# Projet_electronique_final_construct-_PIC.net
KiCad netlist of a schematic drawn in EAGLE
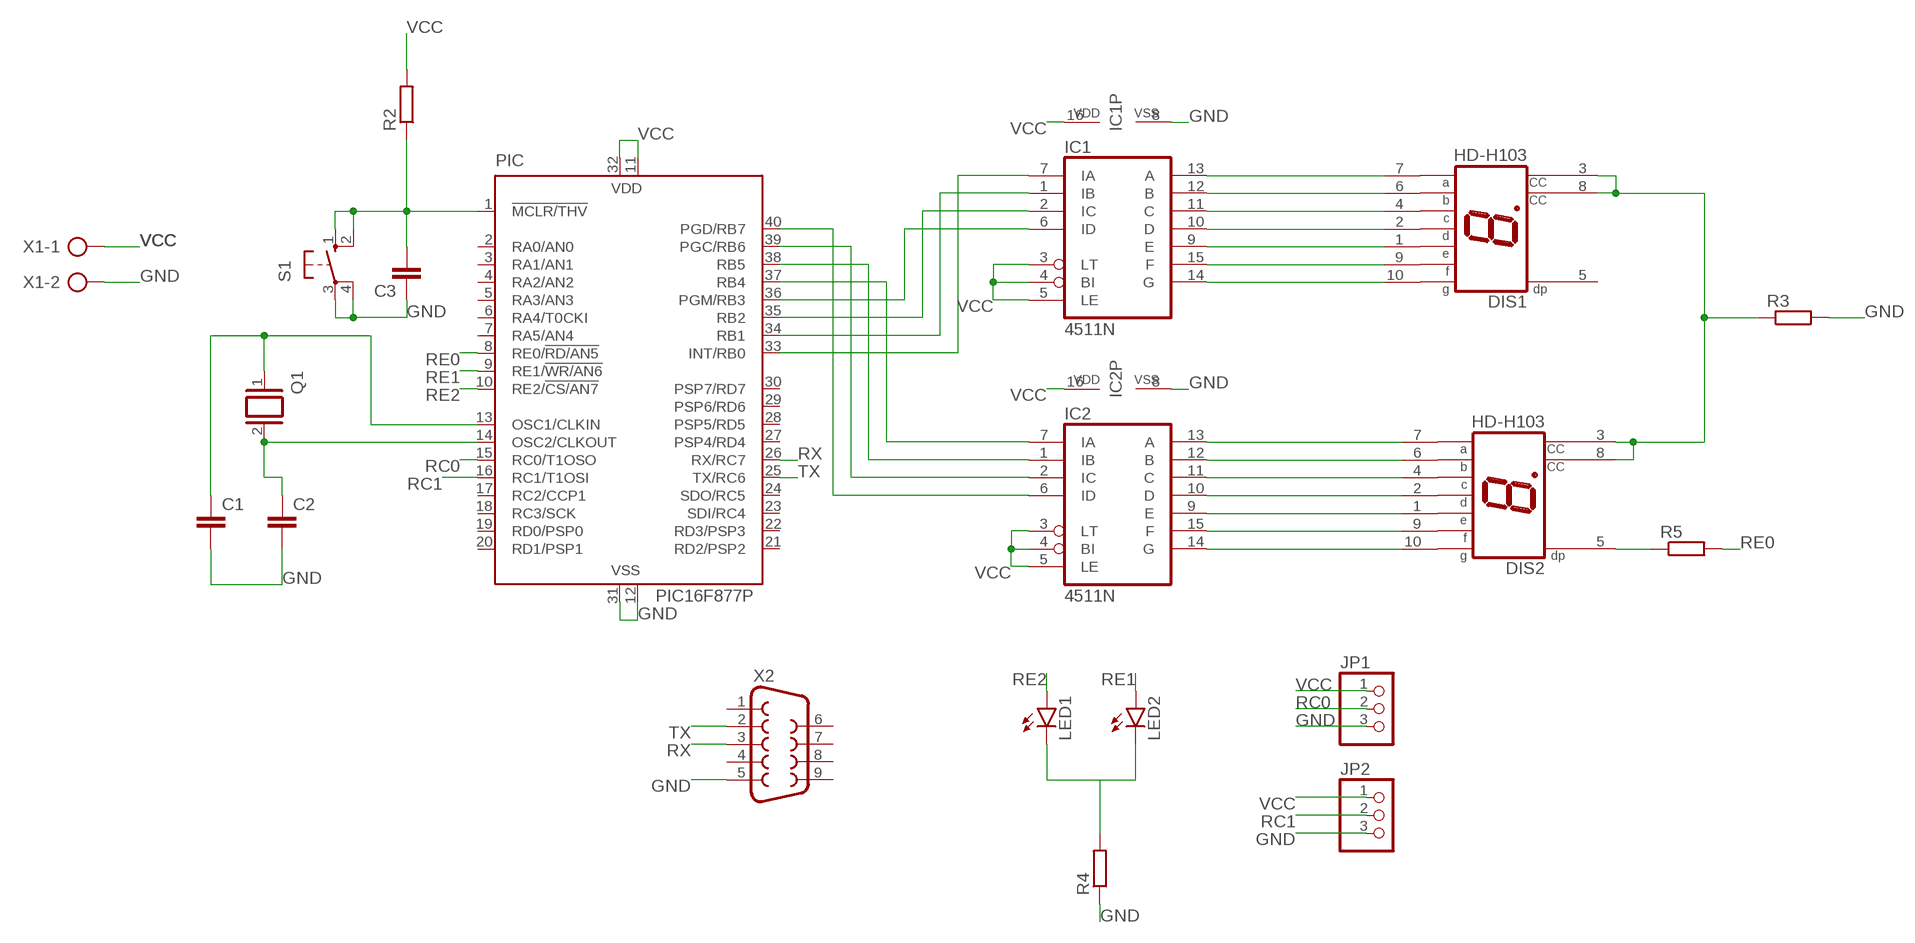
[diagram p0: schematic, sheet 1]

(export (version "E")
  (design (tool "Eeschema 10.0.6"))
  (components
    (comp (ref "C1")
      (value "C-EU025-025X050")
      (footprint "eagle-import:C025-025X050")
      (libsource (lib "eagle-import") (part "C-EU025-025X050"))
    )
    (comp (ref "C2")
      (value "C-EU025-025X050")
      (footprint "eagle-import:C025-025X050")
      (libsource (lib "eagle-import") (part "C-EU025-025X050"))
    )
    (comp (ref "C3")
      (value "C-EU025-025X050")
      (footprint "eagle-import:C025-025X050")
      (libsource (lib "eagle-import") (part "C-EU025-025X050"))
    )
    (comp (ref "DIS1")
      (value "HD-H103")
      (footprint "eagle-import:HDSP-M")
      (libsource (lib "eagle-import") (part "HD-H103"))
    )
    (comp (ref "DIS2")
      (value "HD-H103")
      (footprint "eagle-import:HDSP-M")
      (libsource (lib "eagle-import") (part "HD-H103"))
    )
    (comp (ref "IC1")
      (value "4511N")
      (footprint "eagle-import:DIL16")
      (libsource (lib "eagle-import") (part "4511N"))
    )
    (comp (ref "IC2")
      (value "4511N")
      (footprint "eagle-import:DIL16")
      (libsource (lib "eagle-import") (part "4511N"))
    )
    (comp (ref "JP1")
      (value "PINHD-1X3")
      (footprint "eagle-import:1X03")
      (libsource (lib "eagle-import") (part "PINHD-1X3"))
    )
    (comp (ref "JP2")
      (value "PINHD-1X3")
      (footprint "eagle-import:1X03")
      (libsource (lib "eagle-import") (part "PINHD-1X3"))
    )
    (comp (ref "LED1")
      (value "LED5MM")
      (footprint "eagle-import:LED5MM")
      (libsource (lib "eagle-import") (part "LED5MM"))
    )
    (comp (ref "LED2")
      (value "LED5MM")
      (footprint "eagle-import:LED5MM")
      (libsource (lib "eagle-import") (part "LED5MM"))
    )
    (comp (ref "PIC")
      (value "PIC16F877P")
      (footprint "eagle-import:DIL40")
      (fields (field (name "MF") "MICROCHIP") (field (name "MPN") "PIC16F877-04/P"))
      (libsource (lib "eagle-import") (part "PIC16F87P7"))
    )
    (comp (ref "Q1")
      (value "XTAL/S")
      (footprint "eagle-import:QS")
      (libsource (lib "eagle-import") (part "XTAL/S"))
    )
    (comp (ref "R2")
      (value "R-EU_0207/10")
      (footprint "eagle-import:0207_10")
      (libsource (lib "eagle-import") (part "R-EU_0207/10"))
    )
    (comp (ref "R3")
      (value "R-EU_0207/10")
      (footprint "eagle-import:0207_10")
      (libsource (lib "eagle-import") (part "R-EU_0207/10"))
    )
    (comp (ref "R4")
      (value "R-EU_0207/10")
      (footprint "eagle-import:0207_10")
      (libsource (lib "eagle-import") (part "R-EU_0207/10"))
    )
    (comp (ref "R5")
      (value "R-EU_0207/10")
      (footprint "eagle-import:0207_10")
      (libsource (lib "eagle-import") (part "R-EU_0207/10"))
    )
    (comp (ref "S1")
      (value "10-XX")
      (footprint "eagle-import:B3F-10XX")
      (fields (field (name "MPN") "B3F-1000"))
      (libsource (lib "eagle-import") (part "10-XX"))
    )
    (comp (ref "X1")
      (value "AK300/2")
      (footprint "eagle-import:AK300_2")
      (libsource (lib "eagle-import") (part "AK300/2"))
    )
    (comp (ref "X2")
      (value "F09H")
      (footprint "eagle-import:F09H")
      (libsource (lib "eagle-import") (part "F09H"))
    )
  )
  (nets
    (net (code "1") (name "/GND") (class "Default")
      (node (ref "C1") (pin "2") (pinfunction "2_2") (pintype "passive"))
      (node (ref "C2") (pin "2") (pinfunction "2_2") (pintype "passive"))
      (node (ref "C3") (pin "1") (pinfunction "1_1") (pintype "passive"))
      (node (ref "IC1") (pin "8") (pinfunction "VSS_8") (pintype "power_in"))
      (node (ref "IC2") (pin "8") (pinfunction "VSS_8") (pintype "power_in"))
      (node (ref "JP1") (pin "3") (pinfunction "3_3") (pintype "passive"))
      (node (ref "JP2") (pin "3") (pinfunction "3_3") (pintype "passive"))
      (node (ref "PIC") (pin "12") (pinfunction "VSS_12") (pintype "power_in"))
      (node (ref "PIC") (pin "31") (pinfunction "VSS_31") (pintype "power_in"))
      (node (ref "R3") (pin "2") (pinfunction "2_2") (pintype "passive"))
      (node (ref "R4") (pin "1") (pinfunction "1_1") (pintype "passive"))
      (node (ref "S1") (pin "3") (pinfunction "P_3") (pintype "passive"))
      (node (ref "S1") (pin "4") (pinfunction "P1_4") (pintype "passive"))
      (node (ref "X1") (pin "2") (pinfunction "KL_2") (pintype "passive"))
      (node (ref "X2") (pin "5") (pinfunction "5_5") (pintype "passive"))
    )
    (net (code "2") (name "/RC0") (class "Default")
      (node (ref "JP1") (pin "2") (pinfunction "2_2") (pintype "passive"))
      (node (ref "PIC") (pin "15") (pinfunction "RC0/T1OSO_15") (pintype "bidirectional"))
    )
    (net (code "3") (name "/RC1") (class "Default")
      (node (ref "JP2") (pin "2") (pinfunction "2_2") (pintype "passive"))
      (node (ref "PIC") (pin "16") (pinfunction "RC1/T1OSI_16") (pintype "bidirectional"))
    )
    (net (code "4") (name "/RE0") (class "Default")
      (node (ref "PIC") (pin "8") (pinfunction "RE0/~{RD/AN5}_8") (pintype "bidirectional"))
      (node (ref "R5") (pin "2") (pinfunction "2_2") (pintype "passive"))
    )
    (net (code "5") (name "/RE1") (class "Default")
      (node (ref "LED2") (pin "A") (pinfunction "A_A") (pintype "passive"))
      (node (ref "PIC") (pin "9") (pinfunction "RE1/~{WR/AN6}_9") (pintype "bidirectional"))
    )
    (net (code "6") (name "/RE2") (class "Default")
      (node (ref "LED1") (pin "A") (pinfunction "A_A") (pintype "passive"))
      (node (ref "PIC") (pin "10") (pinfunction "RE2/~{CS/AN7}_10") (pintype "bidirectional"))
    )
    (net (code "7") (name "/RX") (class "Default")
      (node (ref "PIC") (pin "26") (pinfunction "RX/RC7_26") (pintype "bidirectional"))
      (node (ref "X2") (pin "3") (pinfunction "3_3") (pintype "passive"))
    )
    (net (code "8") (name "/TX") (class "Default")
      (node (ref "PIC") (pin "25") (pinfunction "TX/RC6_25") (pintype "bidirectional"))
      (node (ref "X2") (pin "2") (pinfunction "2_2") (pintype "passive"))
    )
    (net (code "9") (name "/VCC") (class "Default")
      (node (ref "IC1") (pin "16") (pinfunction "VDD_16") (pintype "power_in"))
      (node (ref "IC1") (pin "3") (pinfunction "LT_3") (pintype "input"))
      (node (ref "IC1") (pin "4") (pinfunction "BI_4") (pintype "input"))
      (node (ref "IC1") (pin "5") (pinfunction "LE_5") (pintype "input"))
      (node (ref "IC2") (pin "16") (pinfunction "VDD_16") (pintype "power_in"))
      (node (ref "IC2") (pin "3") (pinfunction "LT_3") (pintype "input"))
      (node (ref "IC2") (pin "4") (pinfunction "BI_4") (pintype "input"))
      (node (ref "IC2") (pin "5") (pinfunction "LE_5") (pintype "input"))
      (node (ref "JP1") (pin "1") (pinfunction "1_1") (pintype "passive"))
      (node (ref "JP2") (pin "1") (pinfunction "1_1") (pintype "passive"))
      (node (ref "PIC") (pin "11") (pinfunction "VDD_11") (pintype "power_in"))
      (node (ref "PIC") (pin "32") (pinfunction "VDD_32") (pintype "power_in"))
      (node (ref "R2") (pin "2") (pinfunction "2_2") (pintype "passive"))
      (node (ref "X1") (pin "1") (pinfunction "KL_1") (pintype "passive"))
    )
    (net (code "10") (name "Net-(DIS1-A)") (class "Default")
      (node (ref "DIS1") (pin "7") (pinfunction "A_7") (pintype "passive"))
      (node (ref "IC1") (pin "13") (pinfunction "A_13") (pintype "output"))
    )
    (net (code "11") (name "Net-(DIS1-B)") (class "Default")
      (node (ref "DIS1") (pin "6") (pinfunction "B_6") (pintype "passive"))
      (node (ref "IC1") (pin "12") (pinfunction "B_12") (pintype "output"))
    )
    (net (code "12") (name "Net-(DIS1-C)") (class "Default")
      (node (ref "DIS1") (pin "4") (pinfunction "C_4") (pintype "passive"))
      (node (ref "IC1") (pin "11") (pinfunction "C_11") (pintype "output"))
    )
    (net (code "13") (name "Net-(DIS1-CC-Pad3)") (class "Default")
      (node (ref "DIS1") (pin "3") (pinfunction "CC_3") (pintype "passive"))
      (node (ref "DIS1") (pin "8") (pinfunction "CC_8") (pintype "passive"))
      (node (ref "DIS2") (pin "3") (pinfunction "CC_3") (pintype "passive"))
      (node (ref "DIS2") (pin "8") (pinfunction "CC_8") (pintype "passive"))
      (node (ref "R3") (pin "1") (pinfunction "1_1") (pintype "passive"))
    )
    (net (code "14") (name "Net-(DIS1-D)") (class "Default")
      (node (ref "DIS1") (pin "2") (pinfunction "D_2") (pintype "passive"))
      (node (ref "IC1") (pin "10") (pinfunction "D_10") (pintype "output"))
    )
    (net (code "15") (name "Net-(DIS1-E)") (class "Default")
      (node (ref "DIS1") (pin "1") (pinfunction "E_1") (pintype "passive"))
      (node (ref "IC1") (pin "9") (pinfunction "E_9") (pintype "output"))
    )
    (net (code "16") (name "Net-(DIS1-F)") (class "Default")
      (node (ref "DIS1") (pin "9") (pinfunction "F_9") (pintype "passive"))
      (node (ref "IC1") (pin "15") (pinfunction "F_15") (pintype "output"))
    )
    (net (code "17") (name "Net-(DIS1-G)") (class "Default")
      (node (ref "DIS1") (pin "10") (pinfunction "G_10") (pintype "passive"))
      (node (ref "IC1") (pin "14") (pinfunction "G_14") (pintype "output"))
    )
    (net (code "18") (name "Net-(DIS2-A)") (class "Default")
      (node (ref "DIS2") (pin "7") (pinfunction "A_7") (pintype "passive"))
      (node (ref "IC2") (pin "13") (pinfunction "A_13") (pintype "output"))
    )
    (net (code "19") (name "Net-(DIS2-B)") (class "Default")
      (node (ref "DIS2") (pin "6") (pinfunction "B_6") (pintype "passive"))
      (node (ref "IC2") (pin "12") (pinfunction "B_12") (pintype "output"))
    )
    (net (code "20") (name "Net-(DIS2-C)") (class "Default")
      (node (ref "DIS2") (pin "4") (pinfunction "C_4") (pintype "passive"))
      (node (ref "IC2") (pin "11") (pinfunction "C_11") (pintype "output"))
    )
    (net (code "21") (name "Net-(DIS2-D)") (class "Default")
      (node (ref "DIS2") (pin "2") (pinfunction "D_2") (pintype "passive"))
      (node (ref "IC2") (pin "10") (pinfunction "D_10") (pintype "output"))
    )
    (net (code "22") (name "Net-(DIS2-DP)") (class "Default")
      (node (ref "DIS2") (pin "5") (pinfunction "DP_5") (pintype "passive"))
      (node (ref "R5") (pin "1") (pinfunction "1_1") (pintype "passive"))
    )
    (net (code "23") (name "Net-(DIS2-E)") (class "Default")
      (node (ref "DIS2") (pin "1") (pinfunction "E_1") (pintype "passive"))
      (node (ref "IC2") (pin "9") (pinfunction "E_9") (pintype "output"))
    )
    (net (code "24") (name "Net-(DIS2-F)") (class "Default")
      (node (ref "DIS2") (pin "9") (pinfunction "F_9") (pintype "passive"))
      (node (ref "IC2") (pin "15") (pinfunction "F_15") (pintype "output"))
    )
    (net (code "25") (name "Net-(DIS2-G)") (class "Default")
      (node (ref "DIS2") (pin "10") (pinfunction "G_10") (pintype "passive"))
      (node (ref "IC2") (pin "14") (pinfunction "G_14") (pintype "output"))
    )
    (net (code "26") (name "Net-(IC1A-IA)") (class "Default")
      (node (ref "IC1") (pin "7") (pinfunction "IA_7") (pintype "input"))
      (node (ref "PIC") (pin "33") (pinfunction "INT/RB0_33") (pintype "bidirectional"))
    )
    (net (code "27") (name "Net-(IC1A-IB)") (class "Default")
      (node (ref "IC1") (pin "1") (pinfunction "IB_1") (pintype "input"))
      (node (ref "PIC") (pin "34") (pinfunction "RB1_34") (pintype "bidirectional"))
    )
    (net (code "28") (name "Net-(IC1A-IC)") (class "Default")
      (node (ref "IC1") (pin "2") (pinfunction "IC_2") (pintype "input"))
      (node (ref "PIC") (pin "35") (pinfunction "RB2_35") (pintype "bidirectional"))
    )
    (net (code "29") (name "Net-(IC1A-ID)") (class "Default")
      (node (ref "IC1") (pin "6") (pinfunction "ID_6") (pintype "input"))
      (node (ref "PIC") (pin "36") (pinfunction "PGM/RB3_36") (pintype "bidirectional"))
    )
    (net (code "30") (name "Net-(IC2A-IA)") (class "Default")
      (node (ref "IC2") (pin "7") (pinfunction "IA_7") (pintype "input"))
      (node (ref "PIC") (pin "37") (pinfunction "RB4_37") (pintype "bidirectional"))
    )
    (net (code "31") (name "Net-(IC2A-IB)") (class "Default")
      (node (ref "IC2") (pin "1") (pinfunction "IB_1") (pintype "input"))
      (node (ref "PIC") (pin "38") (pinfunction "RB5_38") (pintype "bidirectional"))
    )
    (net (code "32") (name "Net-(IC2A-IC)") (class "Default")
      (node (ref "IC2") (pin "2") (pinfunction "IC_2") (pintype "input"))
      (node (ref "PIC") (pin "39") (pinfunction "PGC/RB6_39") (pintype "bidirectional"))
    )
    (net (code "33") (name "Net-(IC2A-ID)") (class "Default")
      (node (ref "IC2") (pin "6") (pinfunction "ID_6") (pintype "input"))
      (node (ref "PIC") (pin "40") (pinfunction "PGD/RB7_40") (pintype "bidirectional"))
    )
    (net (code "34") (name "Net-(LED1-C)") (class "Default")
      (node (ref "LED1") (pin "K") (pinfunction "C_K") (pintype "passive"))
      (node (ref "LED2") (pin "K") (pinfunction "C_K") (pintype "passive"))
      (node (ref "R4") (pin "2") (pinfunction "2_2") (pintype "passive"))
    )
    (net (code "35") (name "Net-(PIC-OSC1{slash}CLKIN)") (class "Default")
      (node (ref "C1") (pin "1") (pinfunction "1_1") (pintype "passive"))
      (node (ref "PIC") (pin "13") (pinfunction "OSC1/CLKIN_13") (pintype "input"))
      (node (ref "Q1") (pin "1") (pinfunction "1_1") (pintype "passive"))
    )
    (net (code "36") (name "Net-(PIC-OSC2{slash}CLKOUT)") (class "Default")
      (node (ref "C2") (pin "1") (pinfunction "1_1") (pintype "passive"))
      (node (ref "PIC") (pin "14") (pinfunction "OSC2/CLKOUT_14") (pintype "output"))
      (node (ref "Q1") (pin "2") (pinfunction "2_2") (pintype "passive"))
    )
    (net (code "37") (name "Net-(PIC-~{MCLR{slash}THV})") (class "Default")
      (node (ref "C3") (pin "2") (pinfunction "2_2") (pintype "passive"))
      (node (ref "PIC") (pin "1") (pinfunction "~{MCLR/THV}_1") (pintype "input"))
      (node (ref "R2") (pin "1") (pinfunction "1_1") (pintype "passive"))
      (node (ref "S1") (pin "1") (pinfunction "S_1") (pintype "passive"))
      (node (ref "S1") (pin "2") (pinfunction "S1_2") (pintype "passive"))
    )
    (net (code "38") (name "unconnected-(DIS1-DP-Pad5)") (class "Default")
      (node (ref "DIS1") (pin "5") (pinfunction "DP_5") (pintype "passive"))
    )
    (net (code "39") (name "unconnected-(PIC-PSP4{slash}RD4-Pad27)") (class "Default")
      (node (ref "PIC") (pin "27") (pinfunction "PSP4/RD4_27") (pintype "bidirectional"))
    )
    (net (code "40") (name "unconnected-(PIC-PSP5{slash}RD5-Pad28)") (class "Default")
      (node (ref "PIC") (pin "28") (pinfunction "PSP5/RD5_28") (pintype "bidirectional"))
    )
    (net (code "41") (name "unconnected-(PIC-PSP6{slash}RD6-Pad29)") (class "Default")
      (node (ref "PIC") (pin "29") (pinfunction "PSP6/RD6_29") (pintype "bidirectional"))
    )
    (net (code "42") (name "unconnected-(PIC-PSP7{slash}RD7-Pad30)") (class "Default")
      (node (ref "PIC") (pin "30") (pinfunction "PSP7/RD7_30") (pintype "bidirectional"))
    )
    (net (code "43") (name "unconnected-(PIC-RA0{slash}AN0-Pad2)") (class "Default")
      (node (ref "PIC") (pin "2") (pinfunction "RA0/AN0_2") (pintype "bidirectional"))
    )
    (net (code "44") (name "unconnected-(PIC-RA1{slash}AN1-Pad3)") (class "Default")
      (node (ref "PIC") (pin "3") (pinfunction "RA1/AN1_3") (pintype "bidirectional"))
    )
    (net (code "45") (name "unconnected-(PIC-RA2{slash}AN2-Pad4)") (class "Default")
      (node (ref "PIC") (pin "4") (pinfunction "RA2/AN2_4") (pintype "bidirectional"))
    )
    (net (code "46") (name "unconnected-(PIC-RA3{slash}AN3-Pad5)") (class "Default")
      (node (ref "PIC") (pin "5") (pinfunction "RA3/AN3_5") (pintype "bidirectional"))
    )
    (net (code "47") (name "unconnected-(PIC-RA4{slash}T0CKI-Pad6)") (class "Default")
      (node (ref "PIC") (pin "6") (pinfunction "RA4/T0CKI_6") (pintype "bidirectional"))
    )
    (net (code "48") (name "unconnected-(PIC-RA5{slash}AN4-Pad7)") (class "Default")
      (node (ref "PIC") (pin "7") (pinfunction "RA5/AN4_7") (pintype "bidirectional"))
    )
    (net (code "49") (name "unconnected-(PIC-RC2{slash}CCP1-Pad17)") (class "Default")
      (node (ref "PIC") (pin "17") (pinfunction "RC2/CCP1_17") (pintype "bidirectional"))
    )
    (net (code "50") (name "unconnected-(PIC-RC3{slash}SCK-Pad18)") (class "Default")
      (node (ref "PIC") (pin "18") (pinfunction "RC3/SCK_18") (pintype "bidirectional"))
    )
    (net (code "51") (name "unconnected-(PIC-RD0{slash}PSP0-Pad19)") (class "Default")
      (node (ref "PIC") (pin "19") (pinfunction "RD0/PSP0_19") (pintype "bidirectional"))
    )
    (net (code "52") (name "unconnected-(PIC-RD1{slash}PSP1-Pad20)") (class "Default")
      (node (ref "PIC") (pin "20") (pinfunction "RD1/PSP1_20") (pintype "bidirectional"))
    )
    (net (code "53") (name "unconnected-(PIC-RD2{slash}PSP2-Pad21)") (class "Default")
      (node (ref "PIC") (pin "21") (pinfunction "RD2/PSP2_21") (pintype "bidirectional"))
    )
    (net (code "54") (name "unconnected-(PIC-RD3{slash}PSP3-Pad22)") (class "Default")
      (node (ref "PIC") (pin "22") (pinfunction "RD3/PSP3_22") (pintype "bidirectional"))
    )
    (net (code "55") (name "unconnected-(PIC-SDI{slash}RC4-Pad23)") (class "Default")
      (node (ref "PIC") (pin "23") (pinfunction "SDI/RC4_23") (pintype "bidirectional"))
    )
    (net (code "56") (name "unconnected-(PIC-SDO{slash}RC5-Pad24)") (class "Default")
      (node (ref "PIC") (pin "24") (pinfunction "SDO/RC5_24") (pintype "bidirectional"))
    )
    (net (code "57") (name "unconnected-(X2-Pad1)") (class "Default")
      (node (ref "X2") (pin "1") (pinfunction "1_1") (pintype "passive"))
    )
    (net (code "58") (name "unconnected-(X2-Pad4)") (class "Default")
      (node (ref "X2") (pin "4") (pinfunction "4_4") (pintype "passive"))
    )
    (net (code "59") (name "unconnected-(X2-Pad6)") (class "Default")
      (node (ref "X2") (pin "6") (pinfunction "6_6") (pintype "passive"))
    )
    (net (code "60") (name "unconnected-(X2-Pad7)") (class "Default")
      (node (ref "X2") (pin "7") (pinfunction "7_7") (pintype "passive"))
    )
    (net (code "61") (name "unconnected-(X2-Pad8)") (class "Default")
      (node (ref "X2") (pin "8") (pinfunction "8_8") (pintype "passive"))
    )
    (net (code "62") (name "unconnected-(X2-Pad9)") (class "Default")
      (node (ref "X2") (pin "9") (pinfunction "9_9") (pintype "passive"))
    )
  )
)
